# EAGLE_PCB_Design_Project1_2_DavidSalzman.net
KiCad netlist of a schematic drawn in EAGLE
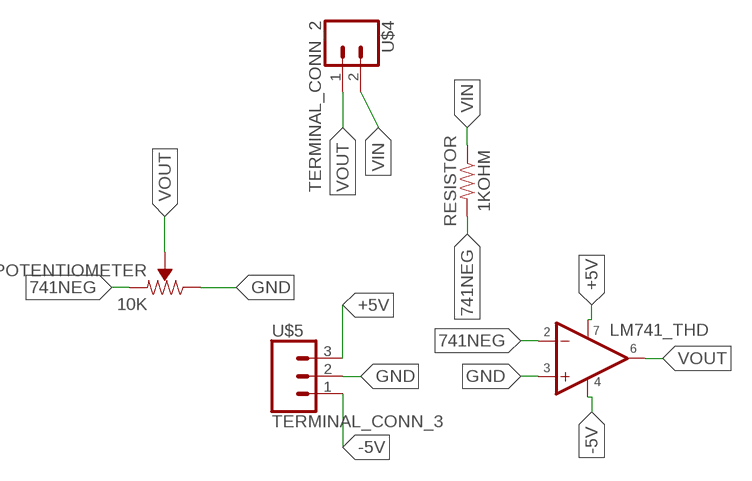
[diagram p0: schematic, sheet 1]

(export (version "E")
  (design (tool "Eeschema 10.0.6"))
  (components
    (comp (ref "1KOHM")
      (value "RESISTOR")
      (footprint "eagle-import:RESISTOR")
      (libsource (lib "eagle-import") (part "RESISTOR"))
    )
    (comp (ref "10K")
      (value "POTENTIOMETER")
      (footprint "eagle-import:POTENTIOMETER")
      (libsource (lib "eagle-import") (part "POTENTIOMETER"))
    )
    (comp (ref "U$1")
      (value "IC-LM741")
      (footprint "eagle-import:IC-LM741")
      (libsource (lib "eagle-import") (part "IC-LM741"))
    )
    (comp (ref "U$4")
      (value "TERMINAL_CONN_2")
      (footprint "eagle-import:TERMINAL_CONN_2")
      (libsource (lib "eagle-import") (part "TERMINAL_CONN_2"))
    )
    (comp (ref "U$5")
      (value "TERMINAL_CONN_3")
      (footprint "eagle-import:TERMINAL-CONN_3")
      (libsource (lib "eagle-import") (part "TERMINAL_CONN_3"))
    )
  )
  (nets
    (net (code "1") (name "+5V") (class "Default")
      (node (ref "U$1") (pin "7") (pinfunction "7_7") (pintype "bidirectional"))
      (node (ref "U$5") (pin "3") (pinfunction "3_3") (pintype "passive"))
    )
    (net (code "2") (name "-5V") (class "Default")
      (node (ref "U$1") (pin "4") (pinfunction "4_4") (pintype "bidirectional"))
      (node (ref "U$5") (pin "1") (pinfunction "1_1") (pintype "passive"))
    )
    (net (code "3") (name "741NEG") (class "Default")
      (node (ref "10K") (pin "3") (pinfunction "CCW_3") (pintype "passive"))
      (node (ref "1KOHM") (pin "2") (pinfunction "2_2") (pintype "passive"))
      (node (ref "U$1") (pin "2") (pinfunction "-IN_2") (pintype "input"))
    )
    (net (code "4") (name "GND") (class "Default")
      (node (ref "10K") (pin "2") (pinfunction "CW_2") (pintype "passive"))
      (node (ref "U$1") (pin "3") (pinfunction "+IN_3") (pintype "input"))
      (node (ref "U$5") (pin "2") (pinfunction "2_2") (pintype "passive"))
    )
    (net (code "5") (name "VIN") (class "Default")
      (node (ref "1KOHM") (pin "1") (pinfunction "1_1") (pintype "passive"))
      (node (ref "U$4") (pin "2") (pinfunction "2_2") (pintype "passive"))
    )
    (net (code "6") (name "VOUT") (class "Default")
      (node (ref "10K") (pin "1") (pinfunction "WIPER_1") (pintype "passive"))
      (node (ref "U$1") (pin "6") (pinfunction "OUT_6") (pintype "output"))
      (node (ref "U$4") (pin "1") (pinfunction "1_1") (pintype "passive"))
    )
  )
)
